# Phy_Daughter_Board_Header.net
KiCad netlist of a schematic drawn in Altium Designer
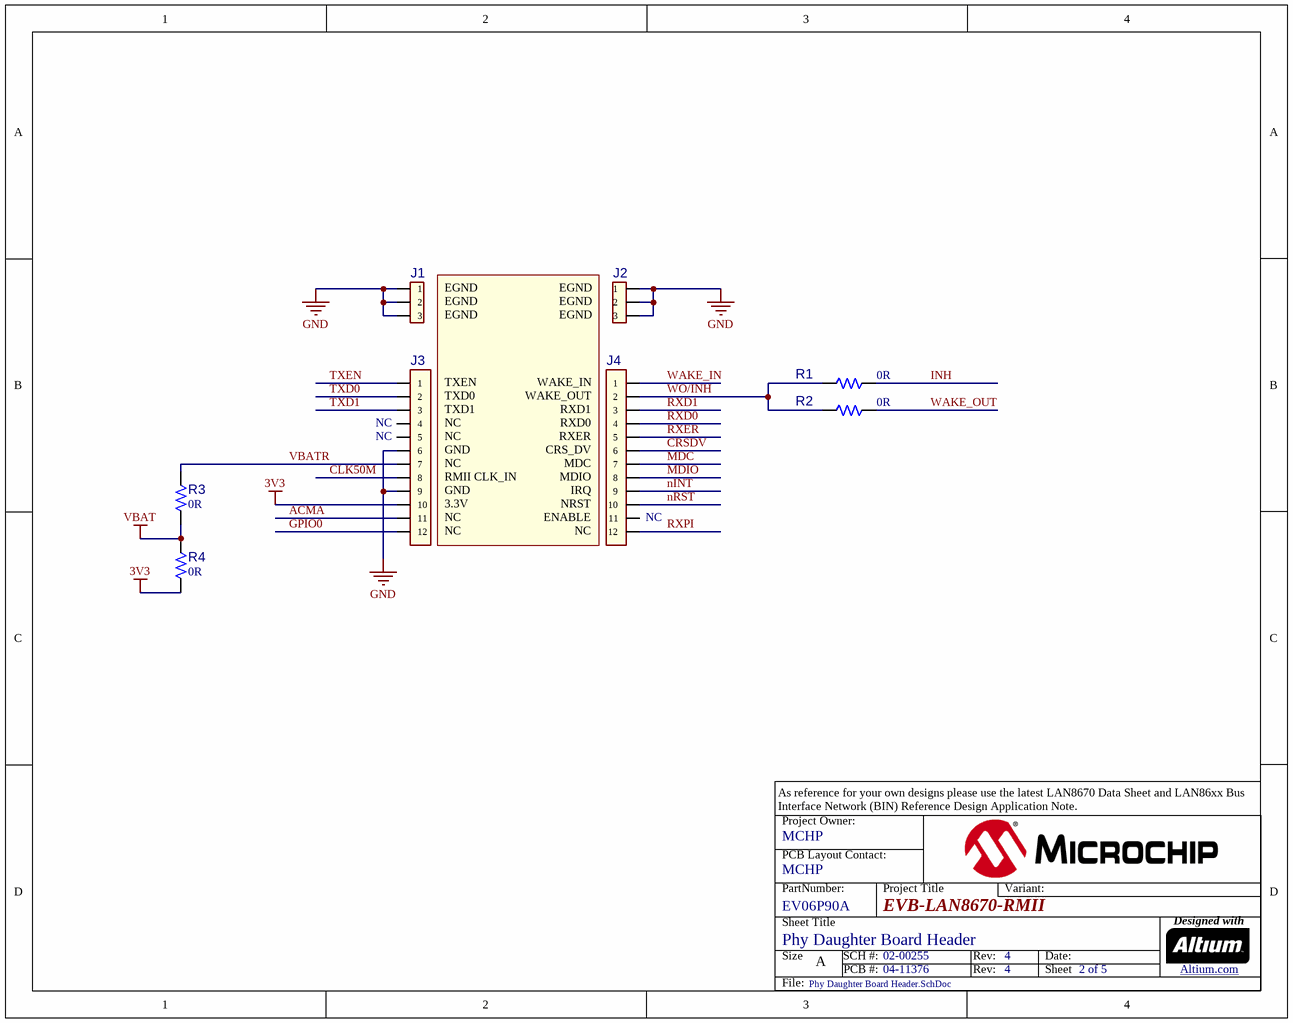
[diagram p0: Phy Daughter Board Header.SchDoc]

(export (version "E")
  (design (tool "Eeschema 10.0.6"))
  (components
    (comp (ref "J1")
      (value "Header 1x3")
      (footprint "HDR_M_1.27_1x3_TMS_103-02_L_S")
      (fields (field (name "OWNER") "Leah Whitaker"))
      (libsource (lib "") (part "Header 1x3_1"))
    )
    (comp (ref "J2")
      (value "Header 1x3")
      (footprint "HDR_M_1.27_1x3_TMS_103-02_L_S")
      (fields (field (name "OWNER") "Leah Whitaker"))
      (libsource (lib "MCHP-CDB-Offline") (part "Header 1x3"))
    )
    (comp (ref "J3")
      (value "Header 1x12")
      (footprint "HDR_M_1.27_1x12")
      (fields (field (name "OWNER") "Leah Whitaker"))
      (libsource (lib "") (part "Header 1x12_1"))
    )
    (comp (ref "J4")
      (value "Header 1x12")
      (footprint "HDR_M_1.27_1x12")
      (fields (field (name "OWNER") "Leah Whitaker"))
      (libsource (lib "MCHP-CDB-Offline") (part "Header 1x12"))
    )
    (comp (ref "R1")
      (value "0R")
      (footprint "RES_C_0402")
      (description "Resistor")
      (fields
        (field (name "TOLERANCE") "50mOhm")
        (field (name "POWER") "1/10W")
        (field (name "OWNER") "Dragos Danaila")
      )
      (libsource (lib "MCHP-CDB") (part "Resistor"))
    )
    (comp (ref "R2")
      (value "0R")
      (footprint "RES_C_0402")
      (description "Resistor")
      (fields
        (field (name "TOLERANCE") "50mOhm")
        (field (name "POWER") "1/10W")
        (field (name "OWNER") "Dragos Danaila")
      )
      (libsource (lib "MCHP-CDB") (part "Resistor"))
    )
    (comp (ref "R3")
      (value "0R")
      (footprint "RES_C_0603")
      (description "Resistor")
      (fields (field (name "POWER") "1/10W") (field (name "OWNER") "Steve Dziaba"))
      (libsource (lib "MCL-Offline") (part "Resistor"))
    )
    (comp (ref "R4")
      (value "0R")
      (footprint "RES_C_0603")
      (description "Resistor")
      (fields (field (name "POWER") "1/10W") (field (name "OWNER") "Steve Dziaba"))
      (libsource (lib "MCL-Offline") (part "Resistor"))
    )
  )
  (nets
    (net (code "1") (name "/ACMA") (class "Default")
      (node (ref "J3") (pin "11") (pinfunction "11_11") (pintype "passive"))
    )
    (net (code "2") (name "/CLK50M") (class "Default")
      (node (ref "J3") (pin "8") (pinfunction "8_8") (pintype "passive"))
    )
    (net (code "3") (name "/CRSDV") (class "Default")
      (node (ref "J4") (pin "6") (pinfunction "6_6") (pintype "passive"))
    )
    (net (code "4") (name "/GPIO0") (class "Default")
      (node (ref "J3") (pin "12") (pinfunction "12_12") (pintype "passive"))
    )
    (net (code "5") (name "/INH") (class "Default")
      (node (ref "R1") (pin "2") (pinfunction "2_2") (pintype "passive"))
    )
    (net (code "6") (name "/MDC") (class "Default")
      (node (ref "J4") (pin "7") (pinfunction "7_7") (pintype "passive"))
    )
    (net (code "7") (name "/MDIO") (class "Default")
      (node (ref "J4") (pin "8") (pinfunction "8_8") (pintype "passive"))
    )
    (net (code "8") (name "/RXD0") (class "Default")
      (node (ref "J4") (pin "4") (pinfunction "4_4") (pintype "passive"))
    )
    (net (code "9") (name "/RXD1") (class "Default")
      (node (ref "J4") (pin "3") (pinfunction "3_3") (pintype "passive"))
    )
    (net (code "10") (name "/RXER") (class "Default")
      (node (ref "J4") (pin "5") (pinfunction "5_5") (pintype "passive"))
    )
    (net (code "11") (name "/RXPI") (class "Default")
      (node (ref "J4") (pin "12") (pinfunction "12_12") (pintype "passive"))
    )
    (net (code "12") (name "/TXD0") (class "Default")
      (node (ref "J3") (pin "2") (pinfunction "2_2") (pintype "passive"))
    )
    (net (code "13") (name "/TXD1") (class "Default")
      (node (ref "J3") (pin "3") (pinfunction "3_3") (pintype "passive"))
    )
    (net (code "14") (name "/TXEN") (class "Default")
      (node (ref "J3") (pin "1") (pinfunction "1_1") (pintype "passive"))
    )
    (net (code "15") (name "/VBATR") (class "Default")
      (node (ref "J3") (pin "7") (pinfunction "7_7") (pintype "passive"))
      (node (ref "R3") (pin "2") (pinfunction "2_2") (pintype "passive"))
    )
    (net (code "16") (name "/WAKE_IN") (class "Default")
      (node (ref "J4") (pin "1") (pinfunction "1_1") (pintype "passive"))
    )
    (net (code "17") (name "/WAKE_OUT") (class "Default")
      (node (ref "R2") (pin "2") (pinfunction "2_2") (pintype "passive"))
    )
    (net (code "18") (name "/WO{slash}INH") (class "Default")
      (node (ref "J4") (pin "2") (pinfunction "2_2") (pintype "passive"))
      (node (ref "R1") (pin "1") (pinfunction "1_1") (pintype "passive"))
      (node (ref "R2") (pin "1") (pinfunction "1_1") (pintype "passive"))
    )
    (net (code "19") (name "/nINT") (class "Default")
      (node (ref "J4") (pin "9") (pinfunction "9_9") (pintype "passive"))
    )
    (net (code "20") (name "/nRST") (class "Default")
      (node (ref "J4") (pin "10") (pinfunction "10_10") (pintype "passive"))
    )
    (net (code "21") (name "3V3") (class "Default")
      (node (ref "J3") (pin "10") (pinfunction "10_10") (pintype "passive"))
      (node (ref "R4") (pin "1") (pinfunction "1_1") (pintype "passive"))
    )
    (net (code "22") (name "GND") (class "Default")
      (node (ref "J1") (pin "1") (pinfunction "1_1") (pintype "passive"))
      (node (ref "J1") (pin "2") (pinfunction "2_2") (pintype "passive"))
      (node (ref "J1") (pin "3") (pinfunction "3_3") (pintype "passive"))
      (node (ref "J2") (pin "1") (pinfunction "1_1") (pintype "passive"))
      (node (ref "J2") (pin "2") (pinfunction "2_2") (pintype "passive"))
      (node (ref "J2") (pin "3") (pinfunction "3_3") (pintype "passive"))
      (node (ref "J3") (pin "6") (pinfunction "6_6") (pintype "passive"))
      (node (ref "J3") (pin "9") (pinfunction "9_9") (pintype "passive"))
    )
    (net (code "23") (name "VBAT") (class "Default")
      (node (ref "R3") (pin "1") (pinfunction "1_1") (pintype "passive"))
      (node (ref "R4") (pin "2") (pinfunction "2_2") (pintype "passive"))
    )
    (net (code "24") (name "unconnected-(J3-Pad4)") (class "Default")
      (node (ref "J3") (pin "4") (pinfunction "4_4") (pintype "passive"))
    )
    (net (code "25") (name "unconnected-(J3-Pad5)") (class "Default")
      (node (ref "J3") (pin "5") (pinfunction "5_5") (pintype "passive"))
    )
    (net (code "26") (name "unconnected-(J4-Pad11)") (class "Default")
      (node (ref "J4") (pin "11") (pinfunction "11_11") (pintype "passive"))
    )
  )
)
